# pintu.net
KiCad netlist of a schematic drawn in EAGLE
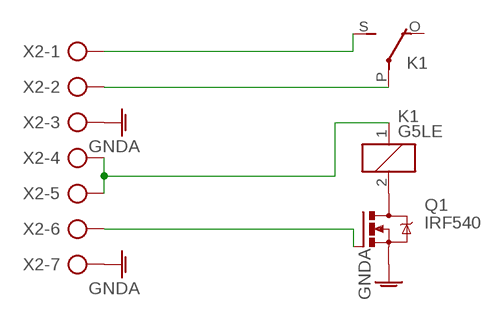
[diagram p0: schematic, sheet 1]

(export (version "E")
  (design (tool "Eeschema 10.0.6"))
  (components
    (comp (ref "K1")
      (value "G5LE")
      (footprint "eagle-import:G5LE")
      (libsource (lib "eagle-import") (part "G5LE"))
    )
    (comp (ref "Q1")
      (value "IRF540")
      (footprint "eagle-import:TO220BV")
      (libsource (lib "eagle-import") (part "IRF540"))
    )
    (comp (ref "X2")
      (value "AK300/7")
      (footprint "eagle-import:AK300_7")
      (libsource (lib "eagle-import") (part "AK300/7"))
    )
  )
  (nets
    (net (code "1") (name "GNDA") (class "Default")
      (node (ref "Q1") (pin "S") (pinfunction "S_S") (pintype "passive"))
      (node (ref "X2") (pin "3") (pinfunction "KL_3") (pintype "passive"))
      (node (ref "X2") (pin "7") (pinfunction "KL_7") (pintype "passive"))
    )
    (net (code "2") (name "Net-(K1-Pad2)") (class "Default")
      (node (ref "K1") (pin "2") (pinfunction "2_2") (pintype "passive"))
      (node (ref "Q1") (pin "D") (pinfunction "D_D") (pintype "passive"))
    )
    (net (code "3") (name "Net-(X2A-KL)") (class "Default")
      (node (ref "K1") (pin "S") (pinfunction "S_S") (pintype "passive"))
      (node (ref "X2") (pin "1") (pinfunction "KL_1") (pintype "passive"))
    )
    (net (code "4") (name "Net-(X2B-KL)") (class "Default")
      (node (ref "K1") (pin "P") (pinfunction "P_P") (pintype "passive"))
      (node (ref "X2") (pin "2") (pinfunction "KL_2") (pintype "passive"))
    )
    (net (code "5") (name "Net-(X2D-KL)") (class "Default")
      (node (ref "K1") (pin "1") (pinfunction "1_1") (pintype "passive"))
      (node (ref "X2") (pin "4") (pinfunction "KL_4") (pintype "passive"))
      (node (ref "X2") (pin "5") (pinfunction "KL_5") (pintype "passive"))
    )
    (net (code "6") (name "Net-(X2F-KL)") (class "Default")
      (node (ref "Q1") (pin "G") (pinfunction "G_G") (pintype "passive"))
      (node (ref "X2") (pin "6") (pinfunction "KL_6") (pintype "passive"))
    )
    (net (code "7") (name "unconnected-(K1-PadO)") (class "Default")
      (node (ref "K1") (pin "O") (pinfunction "O_O") (pintype "passive"))
    )
  )
)
